# us__2shc.net
KiCad netlist of a schematic drawn in Altium Designer
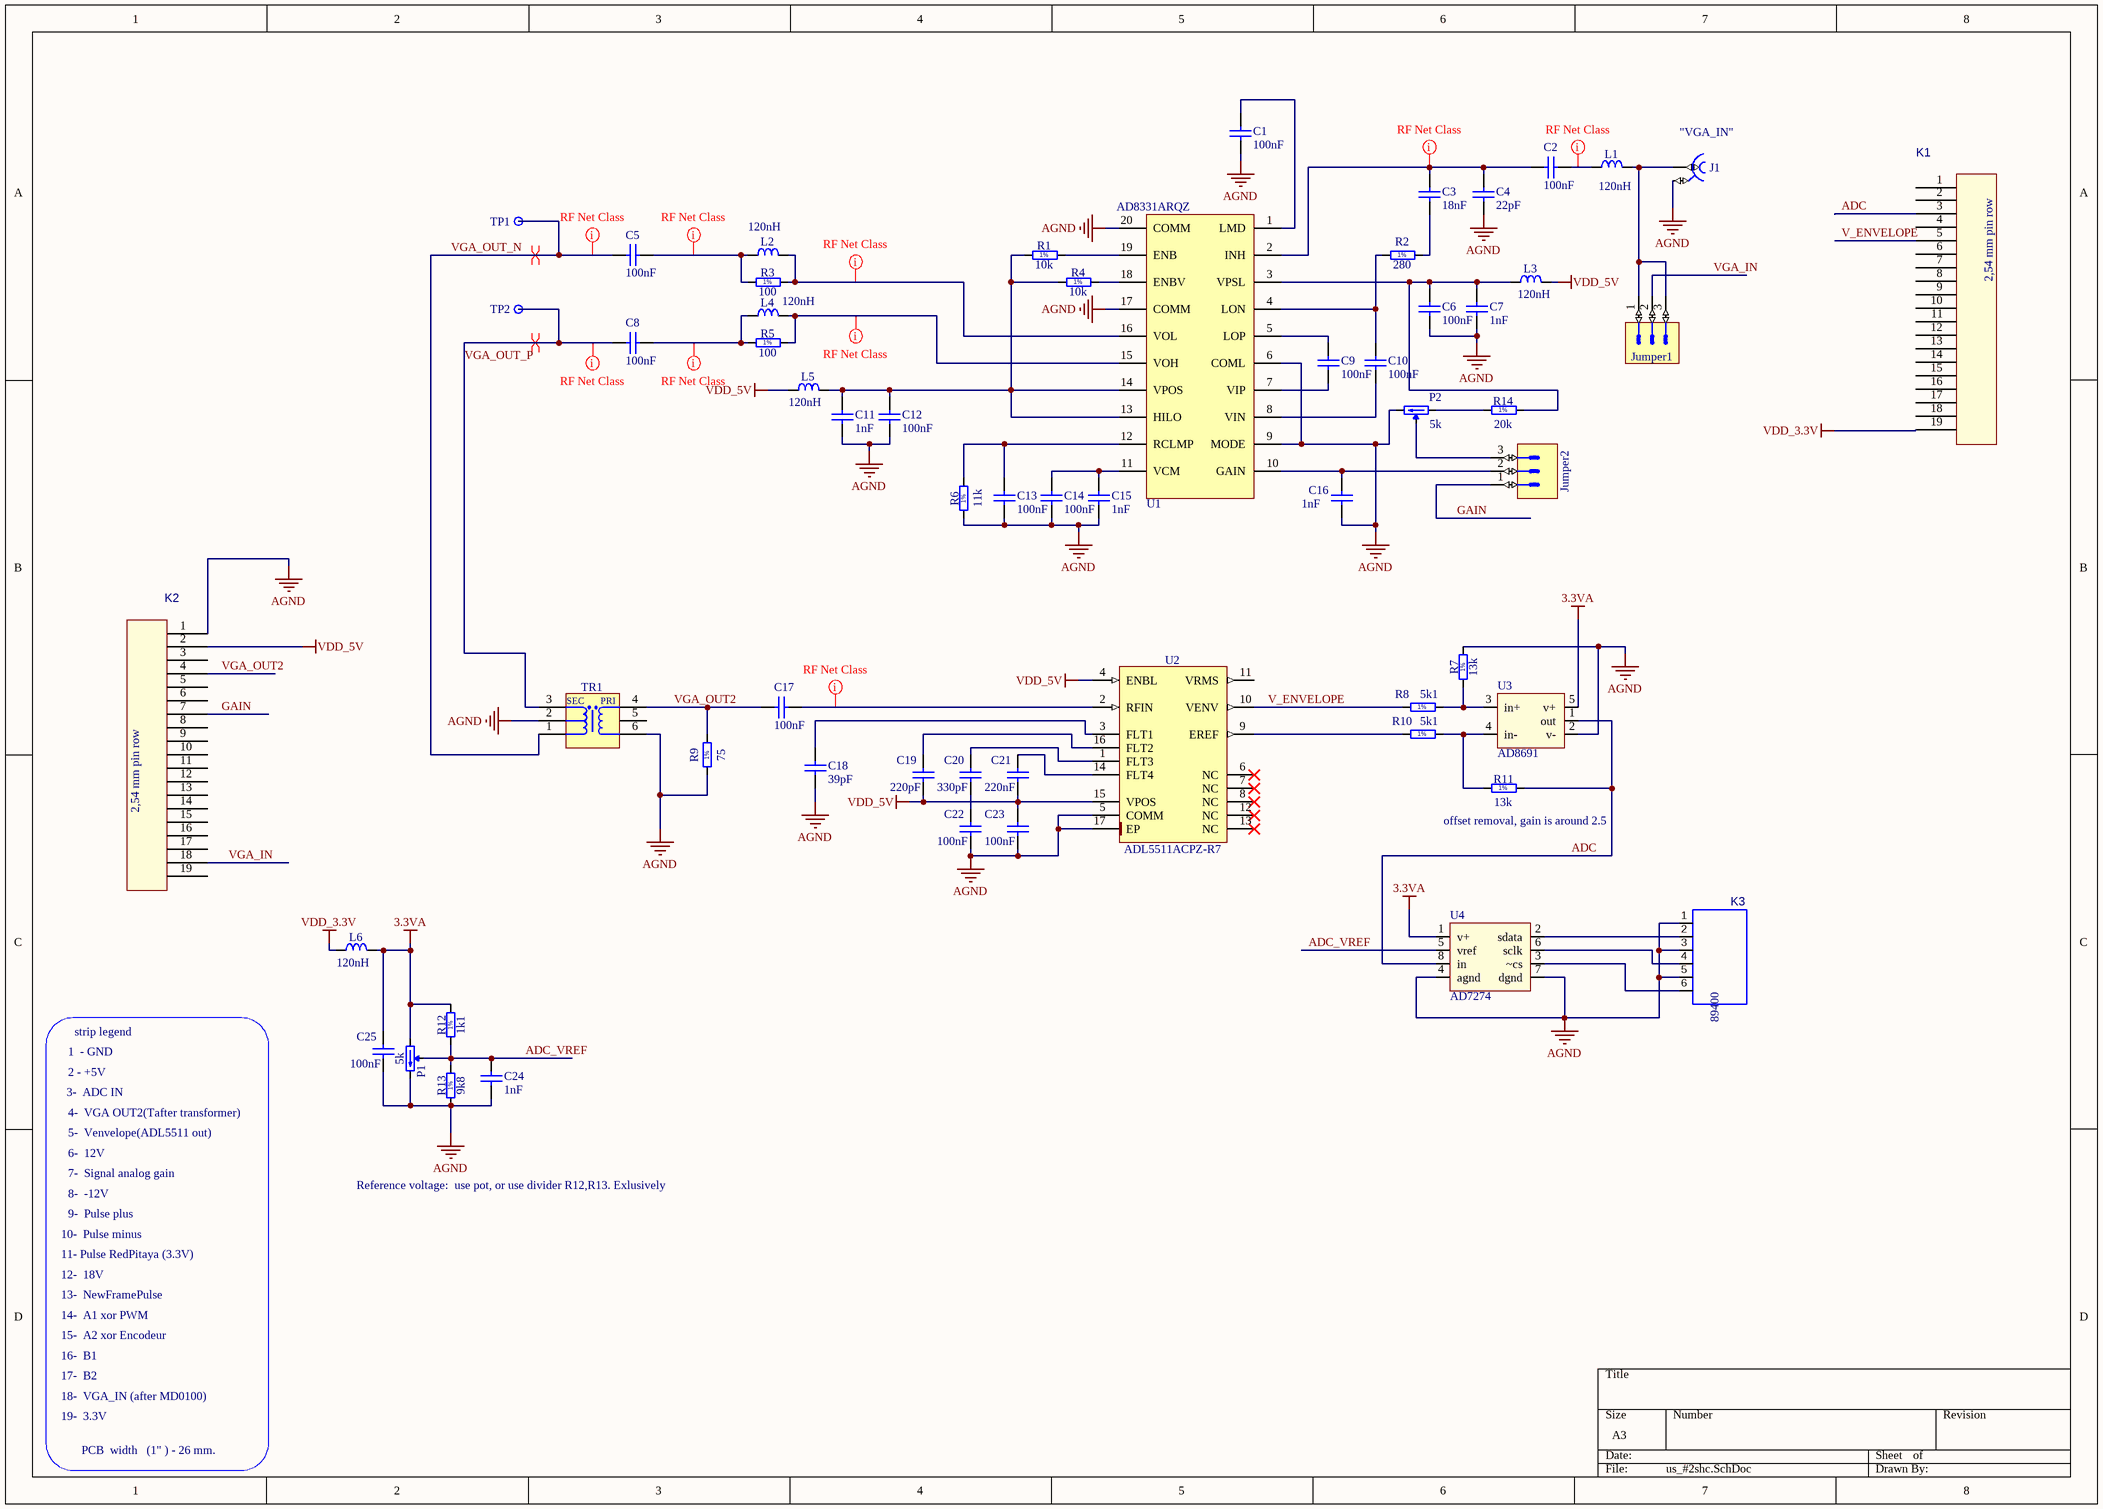
[diagram p0: us_#2shc.SchDoc]

(export (version "E")
  (design (tool "Eeschema 10.0.6"))
  (components
    (comp (ref "C1")
      (value "100nF")
      (footprint "SM0603 _3D_cap")
      (description "Capacitor  0603 inch")
      (fields (field (name "Comment") "cap0603") (field (name "PUBLISHER") "Altium Limited"))
      (libsource (lib "alt_vovan") (part "cap0603"))
    )
    (comp (ref "C2")
      (value "100nF")
      (footprint "SM0603 _3D_cap")
      (description "Capacitor  0603 inch")
      (fields (field (name "Comment") "cap0603") (field (name "PUBLISHER") "Altium Limited"))
      (libsource (lib "alt_vovan") (part "cap0603"))
    )
    (comp (ref "C3")
      (value "18nF")
      (footprint "SM0603 _3D_cap")
      (description "Capacitor  0603 inch")
      (fields (field (name "Comment") "cap0603") (field (name "PUBLISHER") "Altium Limited"))
      (libsource (lib "alt_vovan") (part "cap0603"))
    )
    (comp (ref "C4")
      (value "22pF")
      (footprint "SM0603 _3D_cap")
      (description "Capacitor  0603 inch")
      (fields (field (name "Comment") "cap0603") (field (name "PUBLISHER") "Altium Limited"))
      (libsource (lib "alt_vovan") (part "cap0603"))
    )
    (comp (ref "C5")
      (value "100nF")
      (footprint "SM0603 _3D_cap")
      (description "Capacitor  0603 inch")
      (fields (field (name "Comment") "cap0603") (field (name "PUBLISHER") "Altium Limited"))
      (libsource (lib "alt_vovan") (part "cap0603"))
    )
    (comp (ref "C6")
      (value "100nF")
      (footprint "SM0603 _3D_cap")
      (description "Capacitor  0603 inch")
      (fields (field (name "Comment") "cap0603") (field (name "PUBLISHER") "Altium Limited"))
      (libsource (lib "alt_vovan") (part "cap0603"))
    )
    (comp (ref "C7")
      (value "1nF")
      (footprint "SM0603 _3D_cap")
      (description "Capacitor  0603 inch")
      (fields (field (name "Comment") "cap0603") (field (name "PUBLISHER") "Altium Limited"))
      (libsource (lib "alt_vovan") (part "cap0603"))
    )
    (comp (ref "C8")
      (value "100nF")
      (footprint "SM0603 _3D_cap")
      (description "Capacitor  0603 inch")
      (fields (field (name "Comment") "cap0603") (field (name "PUBLISHER") "Altium Limited"))
      (libsource (lib "alt_vovan") (part "cap0603"))
    )
    (comp (ref "C9")
      (value "100nF")
      (footprint "SM0603 _3D_cap")
      (description "Capacitor  0603 inch")
      (fields (field (name "Comment") "cap0603") (field (name "PUBLISHER") "Altium Limited"))
      (libsource (lib "alt_vovan") (part "cap0603"))
    )
    (comp (ref "C10")
      (value "100nF")
      (footprint "SM0603 _3D_cap")
      (description "Capacitor  0603 inch")
      (fields (field (name "Comment") "cap0603") (field (name "PUBLISHER") "Altium Limited"))
      (libsource (lib "alt_vovan") (part "cap0603"))
    )
    (comp (ref "C11")
      (value "1nF")
      (footprint "SM0603 _3D_cap")
      (description "Capacitor  0603 inch")
      (fields (field (name "Comment") "cap0603") (field (name "PUBLISHER") "Altium Limited"))
      (libsource (lib "alt_vovan") (part "cap0603"))
    )
    (comp (ref "C12")
      (value "100nF")
      (footprint "SM0603 _3D_cap")
      (description "Capacitor  0603 inch")
      (fields (field (name "Comment") "cap0603") (field (name "PUBLISHER") "Altium Limited"))
      (libsource (lib "alt_vovan") (part "cap0603"))
    )
    (comp (ref "C13")
      (value "100nF")
      (footprint "SM0603 _3D_cap")
      (description "Capacitor  0603 inch")
      (fields (field (name "Comment") "cap0603") (field (name "PUBLISHER") "Altium Limited"))
      (libsource (lib "alt_vovan") (part "cap0603"))
    )
    (comp (ref "C14")
      (value "100nF")
      (footprint "SM0603 _3D_cap")
      (description "Capacitor  0603 inch")
      (fields (field (name "Comment") "cap0603") (field (name "PUBLISHER") "Altium Limited"))
      (libsource (lib "alt_vovan") (part "cap0603"))
    )
    (comp (ref "C15")
      (value "1nF")
      (footprint "SM0603 _3D_cap")
      (description "Capacitor  0603 inch")
      (fields (field (name "Comment") "cap0603") (field (name "PUBLISHER") "Altium Limited"))
      (libsource (lib "alt_vovan") (part "cap0603"))
    )
    (comp (ref "C16")
      (value "1nF")
      (footprint "SM0603 _3D_cap")
      (description "Capacitor  0603 inch")
      (fields (field (name "Comment") "cap0603") (field (name "PUBLISHER") "Altium Limited"))
      (libsource (lib "alt_vovan") (part "cap0603"))
    )
    (comp (ref "C17")
      (value "100nF")
      (footprint "SM0603 _3D_cap")
      (description "Capacitor  0603 inch")
      (fields (field (name "Comment") "cap0603") (field (name "PUBLISHER") "Altium Limited"))
      (libsource (lib "alt_vovan") (part "cap0603"))
    )
    (comp (ref "C18")
      (value "39pF")
      (footprint "SM0603 _3D_cap")
      (description "Capacitor  0603 inch")
      (fields (field (name "Comment") "cap0603") (field (name "PUBLISHER") "Altium Limited"))
      (libsource (lib "alt_vovan") (part "cap0603"))
    )
    (comp (ref "C19")
      (value "220pF")
      (footprint "SM0603 _3D_cap")
      (description "Capacitor  0603 inch")
      (fields (field (name "Comment") "cap0603") (field (name "PUBLISHER") "Altium Limited"))
      (libsource (lib "alt_vovan") (part "cap0603"))
    )
    (comp (ref "C20")
      (value "330pF")
      (footprint "SM0603 _3D_cap")
      (description "Capacitor  0603 inch")
      (fields (field (name "Comment") "cap0603") (field (name "PUBLISHER") "Altium Limited"))
      (libsource (lib "alt_vovan") (part "cap0603"))
    )
    (comp (ref "C21")
      (value "220nF")
      (footprint "SM0603 _3D_cap")
      (description "Capacitor  0603 inch")
      (fields (field (name "Comment") "cap0603") (field (name "PUBLISHER") "Altium Limited"))
      (libsource (lib "alt_vovan") (part "cap0603"))
    )
    (comp (ref "C22")
      (value "100nF")
      (footprint "SM0603 _3D_cap")
      (description "Capacitor  0603 inch")
      (fields (field (name "Comment") "cap0603") (field (name "PUBLISHER") "Altium Limited"))
      (libsource (lib "alt_vovan") (part "cap0603"))
    )
    (comp (ref "C23")
      (value "100nF")
      (footprint "SM0603 _3D_cap")
      (description "Capacitor  0603 inch")
      (fields (field (name "Comment") "cap0603") (field (name "PUBLISHER") "Altium Limited"))
      (libsource (lib "alt_vovan") (part "cap0603"))
    )
    (comp (ref "C24")
      (value "1nF")
      (footprint "SM0603 _3D_cap")
      (description "Capacitor  0603 inch")
      (fields (field (name "Comment") "cap0603") (field (name "PUBLISHER") "Altium Limited"))
      (libsource (lib "alt_vovan") (part "cap0603"))
    )
    (comp (ref "C25")
      (value "100nF")
      (footprint "SM0603 _3D_cap")
      (description "Capacitor  0603 inch")
      (fields (field (name "Comment") "cap0603") (field (name "PUBLISHER") "Altium Limited"))
      (libsource (lib "alt_vovan") (part "cap0603"))
    )
    (comp (ref "J1")
      (value "SMA")
      (footprint "AMPHENOL_132357-11")
      (fields
        (field (name "PART NUMBER") "AMPHENOL_132357-11")
        (field (name "MANUFACTURER") "AMPHENOL")
        (field (name "MANUFACTURER PART NUMBER") "132357-11")
        (field (name "AUTHOR") "CERN DEM JLC")
      )
      (libsource (lib "echOpen_ADC_Card") (part "Coax_1Female_1Shield"))
    )
    (comp (ref "Jumper1")
      (value "~")
      (footprint "SULLINS_GRPB031VWVN")
      (description "Connector 3 Male")
      (fields
        (field (name "PART NUMBER") "SULLINS_GRPB031VWVN")
        (field (name "MANUFACTURER") "SULLINS")
        (field (name "AUTHOR") "S. Jafar")
      )
      (libsource (lib "") (part "Connector 3 Male_1"))
    )
    (comp (ref "Jumper2")
      (value "~")
      (footprint "SULLINS_GRPB031VWVN")
      (description "Connector 3 Male")
      (fields
        (field (name "PART NUMBER") "SULLINS_GRPB031VWVN")
        (field (name "MANUFACTURER") "SULLINS")
        (field (name "AUTHOR") "S. Jafar")
      )
      (libsource (lib "Sof-Connectors") (part "Connector 3 Male"))
    )
    (comp (ref "K1")
      (value "PLS_2.54mm-19")
      (footprint "PLS_2.54mm-19")
      (libsource (lib "alt_vovan") (part "PLS_2.54mm-19"))
    )
    (comp (ref "K2")
      (value "PLS_2.54mm-19")
      (footprint "PLS_2.54mm-19")
      (libsource (lib "") (part "PLS_2.54mm-19_1"))
    )
    (comp (ref "K3")
      (value "Molex_89400_061")
      (footprint "Molex_89400-061")
      (description "6 pin vertical 2mm")
      (libsource (lib "alt_vovan") (part "Molex_89400_061"))
    )
    (comp (ref "L1")
      (value "75R@100MHz")
      (footprint "SM_0805_INDUCTANCE _3D")
      (description "chip inductance")
      (fields
        (field (name "PART NUMBER") "IND0805_MURATA_BLM21BB750SN1D")
        (field (name "POWER") "700mA")
        (field (name "AUTHOR") "S. Jafar")
      )
      (libsource (lib "alt_vovan") (part "Ind_Chip"))
    )
    (comp (ref "L2")
      (value "75R@100MHz")
      (footprint "SM_0805_INDUCTANCE _3D")
      (description "chip inductance")
      (fields
        (field (name "PART NUMBER") "IND0805_MURATA_BLM21BB750SN1D")
        (field (name "POWER") "700mA")
        (field (name "AUTHOR") "S. Jafar")
      )
      (libsource (lib "alt_vovan") (part "Ind_Chip"))
    )
    (comp (ref "L3")
      (value "75R@100MHz")
      (footprint "SM_0805_INDUCTANCE _3D")
      (description "chip inductance")
      (fields
        (field (name "PART NUMBER") "IND0805_MURATA_BLM21BB750SN1D")
        (field (name "POWER") "700mA")
        (field (name "AUTHOR") "S. Jafar")
      )
      (libsource (lib "alt_vovan") (part "Ind_Chip"))
    )
    (comp (ref "L4")
      (value "75R@100MHz")
      (footprint "SM_0805_INDUCTANCE _3D")
      (description "chip inductance")
      (fields
        (field (name "PART NUMBER") "IND0805_MURATA_BLM21BB750SN1D")
        (field (name "POWER") "700mA")
        (field (name "AUTHOR") "S. Jafar")
      )
      (libsource (lib "alt_vovan") (part "Ind_Chip"))
    )
    (comp (ref "L5")
      (value "75R@100MHz")
      (footprint "SM_0805_INDUCTANCE _3D")
      (description "chip inductance")
      (fields
        (field (name "PART NUMBER") "IND0805_MURATA_BLM21BB750SN1D")
        (field (name "POWER") "700mA")
        (field (name "AUTHOR") "S. Jafar")
      )
      (libsource (lib "alt_vovan") (part "Ind_Chip"))
    )
    (comp (ref "L6")
      (value "75R@100MHz")
      (footprint "SM_0805_INDUCTANCE _3D")
      (description "chip inductance")
      (fields
        (field (name "PART NUMBER") "IND0805_MURATA_BLM21BB750SN1D")
        (field (name "POWER") "700mA")
        (field (name "AUTHOR") "S. Jafar")
      )
      (libsource (lib "alt_vovan") (part "Ind_Chip"))
    )
    (comp (ref "P1")
      (value "5k")
      (footprint "TRIM_BOURNS_3223W")
      (description "Trimming Potentiometer")
      (fields
        (field (name "PART NUMBER") "TRIM_11T_5K_BOURNS_3223W-1-502E")
        (field (name "POWER") "0.125W")
        (field (name "AUTHOR") "CERN DEM JLC")
      )
      (libsource (lib "echOpen_ADC_Card") (part "Trimming Potentiometer"))
    )
    (comp (ref "P2")
      (value "5k")
      (footprint "TRIM_BOURNS_3223W")
      (description "Trimming Potentiometer")
      (fields
        (field (name "PART NUMBER") "TRIM_11T_5K_BOURNS_3223W-1-502E")
        (field (name "POWER") "0.125W")
        (field (name "AUTHOR") "CERN DEM JLC")
      )
      (libsource (lib "echOpen_ADC_Card") (part "Trimming Potentiometer"))
    )
    (comp (ref "R1")
      (value "10k")
      (footprint "SM0603_3D_res")
      (description "Res_0603_1%_EU")
      (fields
        (field (name "PART NUMBER") "R1206_4K7_1%_0.25W_100PPM")
        (field (name "POWER") "0.25W")
        (field (name "AUTHOR") "CERN DEM JLC")
      )
      (libsource (lib "alt_vovan") (part "Res_0603_1%_EU"))
    )
    (comp (ref "R2")
      (value "280")
      (footprint "SM0603_3D_res")
      (description "Res_0603_1%_EU")
      (fields
        (field (name "PART NUMBER") "R1206_4K7_1%_0.25W_100PPM")
        (field (name "POWER") "0.25W")
        (field (name "AUTHOR") "CERN DEM JLC")
      )
      (libsource (lib "alt_vovan") (part "Res_0603_1%_EU"))
    )
    (comp (ref "R3")
      (value "100")
      (footprint "SM0603_3D_res")
      (description "Res_0603_1%_EU")
      (fields
        (field (name "PART NUMBER") "R1206_4K7_1%_0.25W_100PPM")
        (field (name "POWER") "0.25W")
        (field (name "AUTHOR") "CERN DEM JLC")
      )
      (libsource (lib "alt_vovan") (part "Res_0603_1%_EU"))
    )
    (comp (ref "R4")
      (value "10k")
      (footprint "SM0603_3D_res")
      (description "Res_0603_1%_EU")
      (fields
        (field (name "PART NUMBER") "R1206_4K7_1%_0.25W_100PPM")
        (field (name "POWER") "0.25W")
        (field (name "AUTHOR") "CERN DEM JLC")
      )
      (libsource (lib "alt_vovan") (part "Res_0603_1%_EU"))
    )
    (comp (ref "R5")
      (value "100")
      (footprint "SM0603_3D_res")
      (description "Res_0603_1%_EU")
      (fields
        (field (name "PART NUMBER") "R1206_4K7_1%_0.25W_100PPM")
        (field (name "POWER") "0.25W")
        (field (name "AUTHOR") "CERN DEM JLC")
      )
      (libsource (lib "alt_vovan") (part "Res_0603_1%_EU"))
    )
    (comp (ref "R6")
      (value "11k")
      (footprint "SM0603_3D_res")
      (description "Res_0603_1%_EU")
      (fields
        (field (name "PART NUMBER") "R1206_4K7_1%_0.25W_100PPM")
        (field (name "POWER") "0.25W")
        (field (name "AUTHOR") "CERN DEM JLC")
      )
      (libsource (lib "alt_vovan") (part "Res_0603_1%_EU"))
    )
    (comp (ref "R7")
      (value "13k")
      (footprint "SM0603_3D_res")
      (description "Res_0603_1%_EU")
      (fields
        (field (name "PART NUMBER") "R1206_4K7_1%_0.25W_100PPM")
        (field (name "POWER") "0.25W")
        (field (name "AUTHOR") "CERN DEM JLC")
      )
      (libsource (lib "alt_vovan") (part "Res_0603_1%_EU"))
    )
    (comp (ref "R8")
      (value "5k1")
      (footprint "SM0603_3D_res")
      (description "Res_0603_1%_EU")
      (fields
        (field (name "PART NUMBER") "R1206_4K7_1%_0.25W_100PPM")
        (field (name "POWER") "0.25W")
        (field (name "AUTHOR") "CERN DEM JLC")
      )
      (libsource (lib "alt_vovan") (part "Res_0603_1%_EU"))
    )
    (comp (ref "R9")
      (value "75")
      (footprint "SM0603_3D_res")
      (description "Res_0603_1%_EU")
      (fields
        (field (name "PART NUMBER") "R1206_4K7_1%_0.25W_100PPM")
        (field (name "POWER") "0.25W")
        (field (name "AUTHOR") "CERN DEM JLC")
      )
      (libsource (lib "alt_vovan") (part "Res_0603_1%_EU"))
    )
    (comp (ref "R10")
      (value "5k1")
      (footprint "SM0603_3D_res")
      (description "Res_0603_1%_EU")
      (fields
        (field (name "PART NUMBER") "R1206_4K7_1%_0.25W_100PPM")
        (field (name "POWER") "0.25W")
        (field (name "AUTHOR") "CERN DEM JLC")
      )
      (libsource (lib "alt_vovan") (part "Res_0603_1%_EU"))
    )
    (comp (ref "R11")
      (value "13k")
      (footprint "SM0603_3D_res")
      (description "Res_0603_1%_EU")
      (fields
        (field (name "PART NUMBER") "R1206_4K7_1%_0.25W_100PPM")
        (field (name "POWER") "0.25W")
        (field (name "AUTHOR") "CERN DEM JLC")
      )
      (libsource (lib "alt_vovan") (part "Res_0603_1%_EU"))
    )
    (comp (ref "R12")
      (value "1k1")
      (footprint "SM0603_3D_res")
      (description "Res_0603_1%_EU")
      (fields
        (field (name "PART NUMBER") "R1206_4K7_1%_0.25W_100PPM")
        (field (name "POWER") "0.25W")
        (field (name "AUTHOR") "CERN DEM JLC")
      )
      (libsource (lib "alt_vovan") (part "Res_0603_1%_EU"))
    )
    (comp (ref "R13")
      (value "9k8")
      (footprint "SM0603_3D_res")
      (description "Res_0603_1%_EU")
      (fields
        (field (name "PART NUMBER") "R1206_4K7_1%_0.25W_100PPM")
        (field (name "POWER") "0.25W")
        (field (name "AUTHOR") "CERN DEM JLC")
      )
      (libsource (lib "alt_vovan") (part "Res_0603_1%_EU"))
    )
    (comp (ref "R14")
      (value "20k")
      (footprint "SM0603_3D_res")
      (description "Res_0603_1%_EU")
      (fields
        (field (name "PART NUMBER") "R1206_4K7_1%_0.25W_100PPM")
        (field (name "POWER") "0.25W")
        (field (name "AUTHOR") "CERN DEM JLC")
      )
      (libsource (lib "alt_vovan") (part "Res_0603_1%_EU"))
    )
    (comp (ref "TP1")
      (value "Test Point")
      (footprint "NICOMATIC_C12000B")
      (fields
        (field (name "PART NUMBER") "NICOMATIC_C12000B")
        (field (name "MANUFACTURER") "NICOMATIC")
        (field (name "MANUFACTURER PART NUMBER") "C12000B")
        (field (name "AUTHOR") "CERN DEM JLC")
      )
      (libsource (lib "Sof-Connectors") (part "Test Point"))
    )
    (comp (ref "TP2")
      (value "Test Point")
      (footprint "NICOMATIC_C12000B")
      (fields
        (field (name "PART NUMBER") "NICOMATIC_C12000B")
        (field (name "MANUFACTURER") "NICOMATIC")
        (field (name "MANUFACTURER PART NUMBER") "C12000B")
        (field (name "AUTHOR") "CERN DEM JLC")
      )
      (libsource (lib "Sof-Connectors") (part "Test Point"))
    )
    (comp (ref "TR1")
      (value "1:1")
      (footprint "XFMR_MINI-CIRCUITS_KK81")
      (description "50 Ohm 0.015 To 300MHz RF Transformers")
      (fields
        (field (name "PART NUMBER") "XFMR_MINI-CIRCUITS_T1-6T-KK81")
        (field (name "MANUFACTURER") "MINI-CIRCUITS")
        (field (name "AUTHOR") "S. Jafar")
      )
      (libsource (lib "Sof-Inductors & Transformers") (part "XFMR_MINI-CIRCUITS_T1-6T-KK81"))
    )
    (comp (ref "U1")
      (value "AD8331ARQZ")
      (footprint "SOP64P600X175-20N")
      (fields (field (name "MANUFACTURER") "Analog Devices") (field (name "AUTHOR") "S. Jafar"))
      (libsource (lib "Sof-ICs And Semiconductors") (part "AD8331"))
    )
    (comp (ref "U2")
      (value "ADL5511ACPZ-R7")
      (footprint "QFN50P300X300X80-17N-S175")
      (description "DC to 6 GHz Envelope and TruPwr RMS Detector")
      (fields (field (name "MANUFACTURER") "ANALOG DEVICES") (field (name "AUTHOR") "CERN DEM JLC"))
      (libsource (lib "Sof-ICs And Semiconductors") (part "ADL5511"))
    )
    (comp (ref "U3")
      (value "AD8691")
      (footprint "TSOT-5(RT-5)")
      (libsource (lib "alt_vovan") (part "OpAmp_TSOT5"))
    )
    (comp (ref "U4")
      (value "AD7274")
      (footprint "RM-8")
      (description "adc serial")
      (libsource (lib "alt_vovan") (part "AD7274"))
    )
  )
  (nets
    (net (code "1") (name "/ADC") (class "Default")
      (node (ref "K1") (pin "3") (pinfunction "3_3") (pintype "passive"))
      (node (ref "R11") (pin "2") (pinfunction "2_2") (pintype "passive"))
      (node (ref "U3") (pin "1") (pinfunction "out_1") (pintype "passive"))
      (node (ref "U4") (pin "8") (pinfunction "in_8") (pintype "passive"))
    )
    (net (code "2") (name "/ADC_VREF") (class "Default")
      (node (ref "C24") (pin "2") (pinfunction "2_2") (pintype "passive"))
      (node (ref "P1") (pin "2") (pinfunction "W_2") (pintype "passive"))
      (node (ref "R12") (pin "1") (pinfunction "1_1") (pintype "passive"))
      (node (ref "R13") (pin "2") (pinfunction "2_2") (pintype "passive"))
      (node (ref "U4") (pin "5") (pinfunction "vref_5") (pintype "passive"))
    )
    (net (code "3") (name "/GAIN") (class "Default")
      (node (ref "Jumper2") (pin "1") (pinfunction "1_1") (pintype "bidirectional"))
      (node (ref "K2") (pin "7") (pinfunction "7_7") (pintype "passive"))
    )
    (net (code "4") (name "/VGA_IN") (class "Default")
      (node (ref "Jumper1") (pin "2") (pinfunction "2_2") (pintype "bidirectional"))
      (node (ref "K2") (pin "18") (pinfunction "18_18") (pintype "passive"))
    )
    (net (code "5") (name "/VGA_OUT2") (class "Default")
      (node (ref "C17") (pin "1") (pinfunction "1_1") (pintype "passive"))
      (node (ref "K2") (pin "4") (pinfunction "4_4") (pintype "passive"))
      (node (ref "R9") (pin "2") (pinfunction "2_2") (pintype "passive"))
      (node (ref "TR1") (pin "4") (pinfunction "SDOT_4") (pintype "passive"))
    )
    (net (code "6") (name "/VGA_OUT_N") (class "Default")
      (node (ref "C5") (pin "1") (pinfunction "1_1") (pintype "passive"))
      (node (ref "TP1") (pin "1") (pinfunction "1_1") (pintype "bidirectional"))
      (node (ref "TR1") (pin "1") (pinfunction "P_1") (pintype "passive"))
    )
    (net (code "7") (name "/VGA_OUT_P") (class "Default")
      (node (ref "C8") (pin "2") (pinfunction "2_2") (pintype "passive"))
      (node (ref "TP2") (pin "1") (pinfunction "1_1") (pintype "bidirectional"))
      (node (ref "TR1") (pin "3") (pinfunction "PDOT_3") (pintype "passive"))
    )
    (net (code "8") (name "/V_ENVELOPE") (class "Default")
      (node (ref "K1") (pin "5") (pinfunction "5_5") (pintype "passive"))
      (node (ref "R8") (pin "1") (pinfunction "1_1") (pintype "passive"))
      (node (ref "U2") (pin "10") (pinfunction "VENV_10") (pintype "output"))
    )
    (net (code "9") (name "3.3VA") (class "Default")
      (node (ref "C25") (pin "2") (pinfunction "2_2") (pintype "passive"))
      (node (ref "L6") (pin "2") (pinfunction "2_2") (pintype "passive"))
      (node (ref "P1") (pin "1") (pinfunction "CCW_1") (pintype "passive"))
      (node (ref "R12") (pin "2") (pinfunction "2_2") (pintype "passive"))
      (node (ref "U3") (pin "5") (pinfunction "v+_5") (pintype "passive"))
      (node (ref "U4") (pin "1") (pinfunction "v+_1") (pintype "passive"))
    )
    (net (code "10") (name "AGND") (class "Default")
      (node (ref "C1") (pin "1") (pinfunction "1_1") (pintype "passive"))
      (node (ref "C11") (pin "1") (pinfunction "1_1") (pintype "passive"))
      (node (ref "C12") (pin "1") (pinfunction "1_1") (pintype "passive"))
      (node (ref "C13") (pin "1") (pinfunction "1_1") (pintype "passive"))
      (node (ref "C14") (pin "1") (pinfunction "1_1") (pintype "passive"))
      (node (ref "C15") (pin "1") (pinfunction "1_1") (pintype "passive"))
      (node (ref "C16") (pin "1") (pinfunction "1_1") (pintype "passive"))
      (node (ref "C18") (pin "1") (pinfunction "1_1") (pintype "passive"))
      (node (ref "C22") (pin "1") (pinfunction "1_1") (pintype "passive"))
      (node (ref "C23") (pin "1") (pinfunction "1_1") (pintype "passive"))
      (node (ref "C24") (pin "1") (pinfunction "1_1") (pintype "passive"))
      (node (ref "C25") (pin "1") (pinfunction "1_1") (pintype "passive"))
      (node (ref "C4") (pin "1") (pinfunction "1_1") (pintype "passive"))
      (node (ref "C6") (pin "1") (pinfunction "1_1") (pintype "passive"))
      (node (ref "C7") (pin "1") (pinfunction "1_1") (pintype "passive"))
      (node (ref "J1") (pin "2") (pinfunction "2_2") (pintype "bidirectional"))
      (node (ref "K2") (pin "1") (pinfunction "1_1") (pintype "passive"))
      (node (ref "K3") (pin "1") (pinfunction "1_1") (pintype "passive"))
      (node (ref "K3") (pin "3") (pinfunction "3_3") (pintype "passive"))
      (node (ref "K3") (pin "5") (pinfunction "5_5") (pintype "passive"))
      (node (ref "P1") (pin "3") (pinfunction "CW_3") (pintype "passive"))
      (node (ref "P2") (pin "3") (pinfunction "CW_3") (pintype "passive"))
      (node (ref "R13") (pin "1") (pinfunction "1_1") (pintype "passive"))
      (node (ref "R6") (pin "1") (pinfunction "1_1") (pintype "passive"))
      (node (ref "R7") (pin "2") (pinfunction "2_2") (pintype "passive"))
      (node (ref "R9") (pin "1") (pinfunction "1_1") (pintype "passive"))
      (node (ref "TR1") (pin "2") (pinfunction "NC_2") (pintype "passive"))
      (node (ref "TR1") (pin "6") (pinfunction "S_6") (pintype "passive"))
      (node (ref "U1") (pin "17") (pinfunction "COMM_17") (pintype "passive"))
      (node (ref "U1") (pin "20") (pinfunction "COMM_20") (pintype "passive"))
      (node (ref "U1") (pin "6") (pinfunction "COML_6") (pintype "passive"))
      (node (ref "U1") (pin "9") (pinfunction "MODE_9") (pintype "passive"))
      (node (ref "U2") (pin "17") (pinfunction "EP_17") (pintype "power_in"))
      (node (ref "U2") (pin "5") (pinfunction "COMM_5") (pintype "power_in"))
      (node (ref "U3") (pin "2") (pinfunction "v-_2") (pintype "passive"))
      (node (ref "U4") (pin "4") (pinfunction "agnd_4") (pintype "passive"))
      (node (ref "U4") (pin "7") (pinfunction "dgnd_7") (pintype "passive"))
    )
    (net (code "11") (name "Net-(C2-Pad2)") (class "Default")
      (node (ref "C2") (pin "2") (pinfunction "2_2") (pintype "passive"))
      (node (ref "L1") (pin "1") (pinfunction "1_1") (pintype "passive"))
    )
    (net (code "12") (name "Net-(C3-Pad1)") (class "Default")
      (node (ref "C3") (pin "1") (pinfunction "1_1") (pintype "passive"))
      (node (ref "R2") (pin "2") (pinfunction "2_2") (pintype "passive"))
    )
    (net (code "13") (name "Net-(C5-Pad2)") (class "Default")
      (node (ref "C5") (pin "2") (pinfunction "2_2") (pintype "passive"))
      (node (ref "L2") (pin "1") (pinfunction "1_1") (pintype "passive"))
      (node (ref "R3") (pin "1") (pinfunction "1_1") (pintype "passive"))
    )
    (net (code "14") (name "Net-(C8-Pad1)") (class "Default")
      (node (ref "C8") (pin "1") (pinfunction "1_1") (pintype "passive"))
      (node (ref "L4") (pin "1") (pinfunction "1_1") (pintype "passive"))
      (node (ref "R5") (pin "1") (pinfunction "1_1") (pintype "passive"))
    )
    (net (code "15") (name "Net-(C20-Pad1)") (class "Default")
      (node (ref "C20") (pin "1") (pinfunction "1_1") (pintype "passive"))
      (node (ref "C22") (pin "2") (pinfunction "2_2") (pintype "passive"))
    )
    (net (code "16") (name "Net-(J1-Pad1)") (class "Default")
      (node (ref "J1") (pin "1") (pinfunction "1_1") (pintype "bidirectional"))
      (node (ref "Jumper1") (pin "1") (pinfunction "1_1") (pintype "bidirectional"))
      (node (ref "Jumper1") (pin "3") (pinfunction "3_3") (pintype "bidirectional"))
      (node (ref "L1") (pin "2") (pinfunction "2_2") (pintype "passive"))
    )
    (net (code "17") (name "Net-(P2-CCW)") (class "Default")
      (node (ref "P2") (pin "1") (pinfunction "CCW_1") (pintype "passive"))
      (node (ref "R14") (pin "1") (pinfunction "1_1") (pintype "passive"))
    )
    (net (code "18") (name "Net-(P2-W)") (class "Default")
      (node (ref "Jumper2") (pin "3") (pinfunction "3_3") (pintype "bidirectional"))
      (node (ref "P2") (pin "2") (pinfunction "W_2") (pintype "passive"))
    )
    (net (code "19") (name "Net-(U1-ENB)") (class "Default")
      (node (ref "R1") (pin "2") (pinfunction "2_2") (pintype "passive"))
      (node (ref "U1") (pin "19") (pinfunction "ENB_19") (pintype "passive"))
    )
    (net (code "20") (name "Net-(U1-ENBV)") (class "Default")
      (node (ref "R4") (pin "2") (pinfunction "2_2") (pintype "passive"))
      (node (ref "U1") (pin "18") (pinfunction "ENBV_18") (pintype "passive"))
    )
    (net (code "21") (name "Net-(U1-GAIN)") (class "Default")
      (node (ref "C16") (pin "2") (pinfunction "2_2") (pintype "passive"))
      (node (ref "Jumper2") (pin "2") (pinfunction "2_2") (pintype "bidirectional"))
      (node (ref "U1") (pin "10") (pinfunction "GAIN_10") (pintype "passive"))
    )
    (net (code "22") (name "Net-(U1-HILO)") (class "Default")
      (node (ref "C11") (pin "2") (pinfunction "2_2") (pintype "passive"))
      (node (ref "C12") (pin "2") (pinfunction "2_2") (pintype "passive"))
      (node (ref "L5") (pin "2") (pinfunction "2_2") (pintype "passive"))
      (node (ref "R1") (pin "1") (pinfunction "1_1") (pintype "passive"))
      (node (ref "R4") (pin "1") (pinfunction "1_1") (pintype "passive"))
      (node (ref "U1") (pin "13") (pinfunction "HILO_13") (pintype "passive"))
      (node (ref "U1") (pin "14") (pinfunction "VPOS_14") (pintype "passive"))
    )
    (net (code "23") (name "Net-(U1-INH)") (class "Default")
      (node (ref "C2") (pin "1") (pinfunction "1_1") (pintype "passive"))
      (node (ref "C3") (pin "2") (pinfunction "2_2") (pintype "passive"))
      (node (ref "C4") (pin "2") (pinfunction "2_2") (pintype "passive"))
      (node (ref "U1") (pin "2") (pinfunction "INH_2") (pintype "passive"))
    )
    (net (code "24") (name "Net-(U1-LMD)") (class "Default")
      (node (ref "C1") (pin "2") (pinfunction "2_2") (pintype "passive"))
      (node (ref "U1") (pin "1") (pinfunction "LMD_1") (pintype "passive"))
    )
    (net (code "25") (name "Net-(U1-LON)") (class "Default")
      (node (ref "C10") (pin "2") (pinfunction "2_2") (pintype "passive"))
      (node (ref "R2") (pin "1") (pinfunction "1_1") (pintype "passive"))
      (node (ref "U1") (pin "4") (pinfunction "LON_4") (pintype "passive"))
    )
    (net (code "26") (name "Net-(U1-LOP)") (class "Default")
      (node (ref "C9") (pin "2") (pinfunction "2_2") (pintype "passive"))
      (node (ref "U1") (pin "5") (pinfunction "LOP_5") (pintype "passive"))
    )
    (net (code "27") (name "Net-(U1-RCLMP)") (class "Default")
      (node (ref "C13") (pin "2") (pinfunction "2_2") (pintype "passive"))
      (node (ref "R6") (pin "2") (pinfunction "2_2") (pintype "passive"))
      (node (ref "U1") (pin "12") (pinfunction "RCLMP_12") (pintype "passive"))
    )
    (net (code "28") (name "Net-(U1-VCM)") (class "Default")
      (node (ref "C14") (pin "2") (pinfunction "2_2") (pintype "passive"))
      (node (ref "C15") (pin "2") (pinfunction "2_2") (pintype "passive"))
      (node (ref "U1") (pin "11") (pinfunction "VCM_11") (pintype "passive"))
    )
    (net (code "29") (name "Net-(U1-VIN)") (class "Default")
      (node (ref "C10") (pin "1") (pinfunction "1_1") (pintype "passive"))
      (node (ref "U1") (pin "8") (pinfunction "VIN_8") (pintype "passive"))
    )
    (net (code "30") (name "Net-(U1-VIP)") (class "Default")
      (node (ref "C9") (pin "1") (pinfunction "1_1") (pintype "passive"))
      (node (ref "U1") (pin "7") (pinfunction "VIP_7") (pintype "passive"))
    )
    (net (code "31") (name "Net-(U1-VOH)") (class "Default")
      (node (ref "L4") (pin "2") (pinfunction "2_2") (pintype "passive"))
      (node (ref "R5") (pin "2") (pinfunction "2_2") (pintype "passive"))
      (node (ref "U1") (pin "15") (pinfunction "VOH_15") (pintype "passive"))
    )
    (net (code "32") (name "Net-(U1-VOL)") (class "Default")
      (node (ref "L2") (pin "2") (pinfunction "2_2") (pintype "passive"))
      (node (ref "R3") (pin "2") (pinfunction "2_2") (pintype "passive"))
      (node (ref "U1") (pin "16") (pinfunction "VOL_16") (pintype "passive"))
    )
    (net (code "33") (name "Net-(U1-VPSL)") (class "Default")
      (node (ref "C6") (pin "2") (pinfunction "2_2") (pintype "passive"))
      (node (ref "C7") (pin "2") (pinfunction "2_2") (pintype "passive"))
      (node (ref "L3") (pin "1") (pinfunction "1_1") (pintype "passive"))
      (node (ref "R14") (pin "2") (pinfunction "2_2") (pintype "passive"))
      (node (ref "U1") (pin "3") (pinfunction "VPSL_3") (pintype "passive"))
    )
    (net (code "34") (name "Net-(U2-EREF)") (class "Default")
      (node (ref "R10") (pin "1") (pinfunction "1_1") (pintype "passive"))
      (node (ref "U2") (pin "9") (pinfunction "EREF_9") (pintype "output"))
    )
    (net (code "35") (name "Net-(U2-FLT1)") (class "Default")
      (node (ref "C18") (pin "2") (pinfunction "2_2") (pintype "passive"))
      (node (ref "U2") (pin "3") (pinfunction "FLT1_3") (pintype "passive"))
    )
    (net (code "36") (name "Net-(U2-FLT2)") (class "Default")
      (node (ref "C19") (pin "2") (pinfunction "2_2") (pintype "passive"))
      (node (ref "U2") (pin "16") (pinfunction "FLT2_16") (pintype "passive"))
    )
    (net (code "37") (name "Net-(U2-FLT3)") (class "Default")
      (node (ref "C20") (pin "2") (pinfunction "2_2") (pintype "passive"))
      (node (ref "U2") (pin "1") (pinfunction "FLT3_1") (pintype "passive"))
    )
    (net (code "38") (name "Net-(U2-FLT4)") (class "Default")
      (node (ref "C21") (pin "2") (pinfunction "2_2") (pintype "passive"))
      (node (ref "U2") (pin "14") (pinfunction "FLT4_14") (pintype "passive"))
    )
    (net (code "39") (name "Net-(U2-RFIN)") (class "Default")
      (node (ref "C17") (pin "2") (pinfunction "2_2") (pintype "passive"))
      (node (ref "U2") (pin "2") (pinfunction "RFIN_2") (pintype "input"))
    )
    (net (code "40") (name "Net-(U3-in+)") (class "Default")
      (node (ref "R7") (pin "1") (pinfunction "1_1") (pintype "passive"))
      (node (ref "R8") (pin "2") (pinfunction "2_2") (pintype "passive"))
      (node (ref "U3") (pin "3") (pinfunction "in+_3") (pintype "passive"))
    )
    (net (code "41") (name "Net-(U3-in-)") (class "Default")
      (node (ref "R10") (pin "2") (pinfunction "2_2") (pintype "passive"))
      (node (ref "R11") (pin "1") (pinfunction "1_1") (pintype "passive"))
      (node (ref "U3") (pin "4") (pinfunction "in-_4") (pintype "passive"))
    )
    (net (code "42") (name "Net-(U4-sclk)") (class "Default")
      (node (ref "K3") (pin "4") (pinfunction "4_4") (pintype "passive"))
      (node (ref "U4") (pin "6") (pinfunction "sclk_6") (pintype "passive"))
    )
    (net (code "43") (name "Net-(U4-sdata)") (class "Default")
      (node (ref "K3") (pin "2") (pinfunction "2_2") (pintype "passive"))
      (node (ref "U4") (pin "2") (pinfunction "sdata_2") (pintype "passive"))
    )
    (net (code "44") (name "Net-(U4-~cs)") (class "Default")
      (node (ref "K3") (pin "6") (pinfunction "6_6") (pintype "passive"))
      (node (ref "U4") (pin "3") (pinfunction "~cs_3") (pintype "passive"))
    )
    (net (code "45") (name "VDD_3.3V") (class "Default")
      (node (ref "K1") (pin "19") (pinfunction "19_19") (pintype "passive"))
      (node (ref "L6") (pin "1") (pinfunction "1_1") (pintype "passive"))
    )
    (net (code "46") (name "VDD_5V") (class "Default")
      (node (ref "C19") (pin "1") (pinfunction "1_1") (pintype "passive"))
      (node (ref "C21") (pin "1") (pinfunction "1_1") (pintype "passive"))
      (node (ref "C23") (pin "2") (pinfunction "2_2") (pintype "passive"))
      (node (ref "K2") (pin "2") (pinfunction "2_2") (pintype "passive"))
      (node (ref "L3") (pin "2") (pinfunction "2_2") (pintype "passive"))
      (node (ref "L5") (pin "1") (pinfunction "1_1") (pintype "passive"))
      (node (ref "U2") (pin "15") (pinfunction "VPOS_15") (pintype "power_in"))
      (node (ref "U2") (pin "4") (pinfunction "ENBL_4") (pintype "input"))
    )
    (net (code "47") (name "unconnected-(K1-Pad1)") (class "Default")
      (node (ref "K1") (pin "1") (pinfunction "1_1") (pintype "passive"))
    )
    (net (code "48") (name "unconnected-(K1-Pad2)") (class "Default")
      (node (ref "K1") (pin "2") (pinfunction "2_2") (pintype "passive"))
    )
    (net (code "49") (name "unconnected-(K1-Pad4)") (class "Default")
      (node (ref "K1") (pin "4") (pinfunction "4_4") (pintype "passive"))
    )
    (net (code "50") (name "unconnected-(K1-Pad6)") (class "Default")
      (node (ref "K1") (pin "6") (pinfunction "6_6") (pintype "passive"))
    )
    (net (code "51") (name "unconnected-(K1-Pad7)") (class "Default")
      (node (ref "K1") (pin "7") (pinfunction "7_7") (pintype "passive"))
    )
    (net (code "52") (name "unconnected-(K1-Pad8)") (class "Default")
      (node (ref "K1") (pin "8") (pinfunction "8_8") (pintype "passive"))
    )
    (net (code "53") (name "unconnected-(K1-Pad9)") (class "Default")
      (node (ref "K1") (pin "9") (pinfunction "9_9") (pintype "passive"))
    )
    (net (code "54") (name "unconnected-(K1-Pad10)") (class "Default")
      (node (ref "K1") (pin "10") (pinfunction "10_10") (pintype "passive"))
    )
    (net (code "55") (name "unconnected-(K1-Pad11)") (class "Default")
      (node (ref "K1") (pin "11") (pinfunction "11_11") (pintype "passive"))
    )
    (net (code "56") (name "unconnected-(K1-Pad12)") (class "Default")
      (node (ref "K1") (pin "12") (pinfunction "12_12") (pintype "passive"))
    )
    (net (code "57") (name "unconnected-(K1-Pad13)") (class "Default")
      (node (ref "K1") (pin "13") (pinfunction "13_13") (pintype "passive"))
    )
    (net (code "58") (name "unconnected-(K1-Pad14)") (class "Default")
      (node (ref "K1") (pin "14") (pinfunction "14_14") (pintype "passive"))
    )
    (net (code "59") (name "unconnected-(K1-Pad15)") (class "Default")
      (node (ref "K1") (pin "15") (pinfunction "15_15") (pintype "passive"))
    )
    (net (code "60") (name "unconnected-(K1-Pad16)") (class "Default")
      (node (ref "K1") (pin "16") (pinfunction "16_16") (pintype "passive"))
    )
    (net (code "61") (name "unconnected-(K1-Pad17)") (class "Default")
      (node (ref "K1") (pin "17") (pinfunction "17_17") (pintype "passive"))
    )
    (net (code "62") (name "unconnected-(K1-Pad18)") (class "Default")
      (node (ref "K1") (pin "18") (pinfunction "18_18") (pintype "passive"))
    )
    (net (code "63") (name "unconnected-(K2-Pad3)") (class "Default")
      (node (ref "K2") (pin "3") (pinfunction "3_3") (pintype "passive"))
    )
    (net (code "64") (name "unconnected-(K2-Pad5)") (class "Default")
      (node (ref "K2") (pin "5") (pinfunction "5_5") (pintype "passive"))
    )
    (net (code "65") (name "unconnected-(K2-Pad6)") (class "Default")
      (node (ref "K2") (pin "6") (pinfunction "6_6") (pintype "passive"))
    )
    (net (code "66") (name "unconnected-(K2-Pad8)") (class "Default")
      (node (ref "K2") (pin "8") (pinfunction "8_8") (pintype "passive"))
    )
    (net (code "67") (name "unconnected-(K2-Pad9)") (class "Default")
      (node (ref "K2") (pin "9") (pinfunction "9_9") (pintype "passive"))
    )
    (net (code "68") (name "unconnected-(K2-Pad10)") (class "Default")
      (node (ref "K2") (pin "10") (pinfunction "10_10") (pintype "passive"))
    )
    (net (code "69") (name "unconnected-(K2-Pad11)") (class "Default")
      (node (ref "K2") (pin "11") (pinfunction "11_11") (pintype "passive"))
    )
    (net (code "70") (name "unconnected-(K2-Pad12)") (class "Default")
      (node (ref "K2") (pin "12") (pinfunction "12_12") (pintype "passive"))
    )
    (net (code "71") (name "unconnected-(K2-Pad13)") (class "Default")
      (node (ref "K2") (pin "13") (pinfunction "13_13") (pintype "passive"))
    )
    (net (code "72") (name "unconnected-(K2-Pad14)") (class "Default")
      (node (ref "K2") (pin "14") (pinfunction "14_14") (pintype "passive"))
    )
    (net (code "73") (name "unconnected-(K2-Pad15)") (class "Default")
      (node (ref "K2") (pin "15") (pinfunction "15_15") (pintype "passive"))
    )
    (net (code "74") (name "unconnected-(K2-Pad16)") (class "Default")
      (node (ref "K2") (pin "16") (pinfunction "16_16") (pintype "passive"))
    )
    (net (code "75") (name "unconnected-(K2-Pad17)") (class "Default")
      (node (ref "K2") (pin "17") (pinfunction "17_17") (pintype "passive"))
    )
    (net (code "76") (name "unconnected-(K2-Pad19)") (class "Default")
      (node (ref "K2") (pin "19") (pinfunction "19_19") (pintype "passive"))
    )
    (net (code "77") (name "unconnected-(TR1-NC-Pad5)") (class "Default")
      (node (ref "TR1") (pin "5") (pinfunction "NC_5") (pintype "passive"))
    )
    (net (code "78") (name "unconnected-(U2-NC-Pad6)") (class "Default")
      (node (ref "U2") (pin "6") (pinfunction "NC_6") (pintype "passive+no_connect"))
    )
    (net (code "79") (name "unconnected-(U2-NC-Pad7)") (class "Default")
      (node (ref "U2") (pin "7") (pinfunction "NC_7") (pintype "passive+no_connect"))
    )
    (net (code "80") (name "unconnected-(U2-NC-Pad8)") (class "Default")
      (node (ref "U2") (pin "8") (pinfunction "NC_8") (pintype "passive+no_connect"))
    )
    (net (code "81") (name "unconnected-(U2-NC-Pad12)") (class "Default")
      (node (ref "U2") (pin "12") (pinfunction "NC_12") (pintype "passive+no_connect"))
    )
    (net (code "82") (name "unconnected-(U2-NC-Pad13)") (class "Default")
      (node (ref "U2") (pin "13") (pinfunction "NC_13") (pintype "passive+no_connect"))
    )
    (net (code "83") (name "unconnected-(U2-VRMS-Pad11)") (class "Default")
      (node (ref "U2") (pin "11") (pinfunction "VRMS_11") (pintype "output"))
    )
  )
)
